# CONNECTOR_BUFFER.net
KiCad netlist of a schematic drawn in Altium Designer
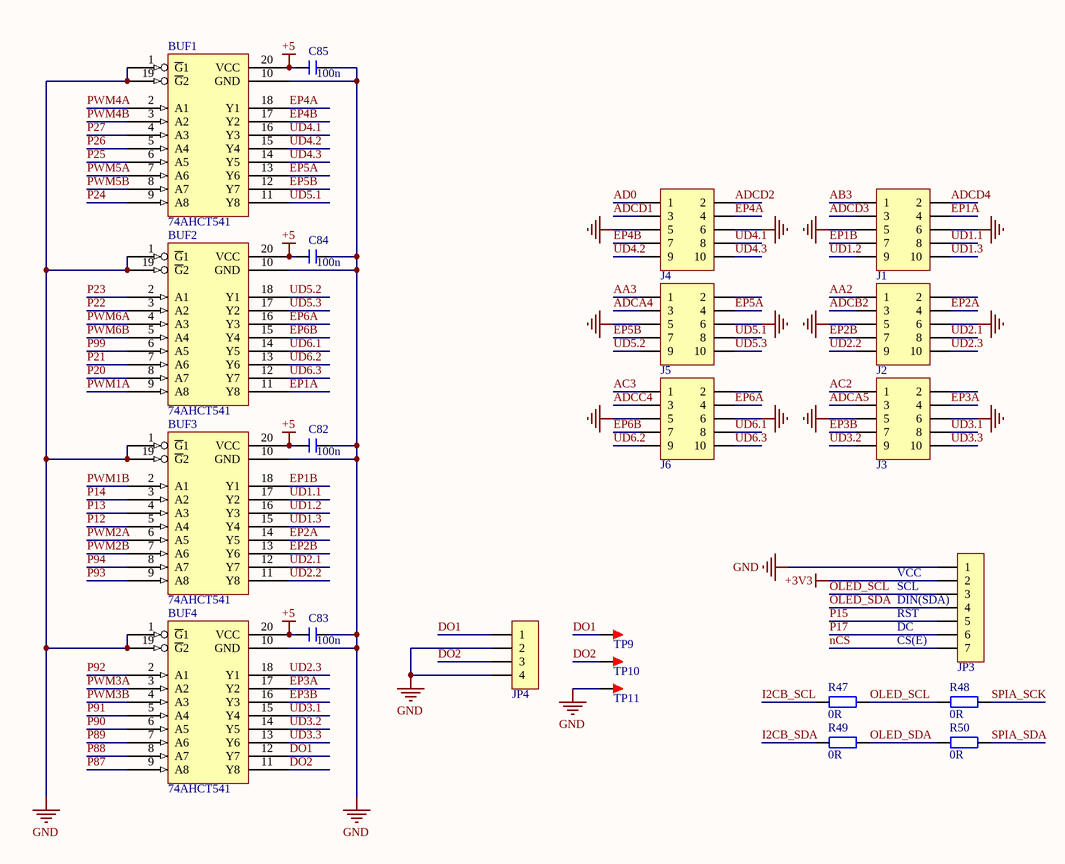
[diagram p0: CONNECTOR_BUFFER.SchDoc]

(export (version "E")
  (design (tool "Eeschema 10.0.6"))
  (components
    (comp (ref "BUF1")
      (value "74AHCT541")
      (footprint "TSSOP20_N")
      (libsource (lib "34 - 74系列芯片 -带电源") (part "74AHCT541"))
    )
    (comp (ref "BUF2")
      (value "74AHCT541")
      (footprint "TSSOP20_N")
      (libsource (lib "34 - 74系列芯片 -带电源") (part "74AHCT541"))
    )
    (comp (ref "BUF3")
      (value "74AHCT541")
      (footprint "TSSOP20_N")
      (libsource (lib "34 - 74系列芯片 -带电源") (part "74AHCT541"))
    )
    (comp (ref "BUF4")
      (value "74AHCT541")
      (footprint "TSSOP20_N")
      (libsource (lib "34 - 74系列芯片 -带电源") (part "74AHCT541"))
    )
    (comp (ref "C82")
      (value "100n")
      (footprint "C 0805_L")
      (description "贴片电容")
      (libsource (lib "01 - 电容-电阻-电感") (part "C"))
    )
    (comp (ref "C83")
      (value "100n")
      (footprint "C 0805_L")
      (description "贴片电容")
      (libsource (lib "01 - 电容-电阻-电感") (part "C"))
    )
    (comp (ref "C84")
      (value "100n")
      (footprint "C 0805_L")
      (description "贴片电容")
      (libsource (lib "01 - 电容-电阻-电感") (part "C"))
    )
    (comp (ref "C85")
      (value "100n")
      (footprint "C 0805_L")
      (description "贴片电容")
      (libsource (lib "01 - 电容-电阻-电感") (part "C"))
    )
    (comp (ref "J1")
      (value "Header 5X2")
      (footprint "IDC2.54-LI-2x5P")
      (description "5*2P接插件")
      (libsource (lib "18 - 接插件-脚距2.54mm (100mil) ") (part "Header 5X2"))
    )
    (comp (ref "J2")
      (value "Header 5X2")
      (footprint "IDC2.54-LI-2x5P")
      (description "5*2P接插件")
      (libsource (lib "18 - 接插件-脚距2.54mm (100mil) ") (part "Header 5X2"))
    )
    (comp (ref "J3")
      (value "Header 5X2")
      (footprint "IDC2.54-LI-2x5P")
      (description "5*2P接插件")
      (libsource (lib "18 - 接插件-脚距2.54mm (100mil) ") (part "Header 5X2"))
    )
    (comp (ref "J4")
      (value "Header 5X2")
      (footprint "IDC2.54-LI-2x5P")
      (description "5*2P接插件")
      (libsource (lib "18 - 接插件-脚距2.54mm (100mil) ") (part "Header 5X2"))
    )
    (comp (ref "J5")
      (value "Header 5X2")
      (footprint "IDC2.54-LI-2x5P")
      (description "5*2P接插件")
      (libsource (lib "18 - 接插件-脚距2.54mm (100mil) ") (part "Header 5X2"))
    )
    (comp (ref "J6")
      (value "Header 5X2")
      (footprint "IDC2.54-LI-2x5P")
      (description "5*2P接插件")
      (libsource (lib "18 - 接插件-脚距2.54mm (100mil) ") (part "Header 5X2"))
    )
    (comp (ref "JP3")
      (value "HDR-1X7")
      (footprint "HDR2.54-M-LI-7P")
      (description "7P接插件")
      (libsource (lib "18 - 接插件-脚距2.54mm (100mil) ") (part "Header 7"))
    )
    (comp (ref "JP4")
      (value "HDR-1X4")
      (footprint "HDR2.54-LI-4P")
      (description "4P接插件")
      (libsource (lib "18 - 接插件-脚距2.54mm (100mil) ") (part "Header 4"))
    )
    (comp (ref "R47")
      (value "0R")
      (footprint "R 0805_L")
      (description "贴片电阻")
      (libsource (lib "01 - 电容-电阻-电感") (part "R"))
    )
    (comp (ref "R48")
      (value "0R")
      (footprint "R 0805_L")
      (description "贴片电阻")
      (libsource (lib "01 - 电容-电阻-电感") (part "R"))
    )
    (comp (ref "R49")
      (value "0R")
      (footprint "R 0805_L")
      (description "贴片电阻")
      (libsource (lib "01 - 电容-电阻-电感") (part "R"))
    )
    (comp (ref "R50")
      (value "0R")
      (footprint "R 0805_L")
      (description "贴片电阻")
      (libsource (lib "01 - 电容-电阻-电感") (part "R"))
    )
    (comp (ref "TP9")
      (value "TEST TP")
      (footprint "TEST TP1.4_B")
      (description "测试环")
      (libsource (lib "10 - 未分类元器件") (part "TEST TP"))
    )
    (comp (ref "TP10")
      (value "TEST TP")
      (footprint "TEST TP1.4_B")
      (description "测试环")
      (libsource (lib "10 - 未分类元器件") (part "TEST TP"))
    )
    (comp (ref "TP11")
      (value "TEST TP")
      (footprint "TEST TP1.4_B")
      (description "测试环")
      (libsource (lib "10 - 未分类元器件") (part "TEST TP"))
    )
  )
  (nets
    (net (code "1") (name "+3V3") (class "Default")
      (node (ref "JP3") (pin "2") (pinfunction "2_2") (pintype "passive"))
    )
    (net (code "2") (name "+5") (class "Default")
      (node (ref "BUF1") (pin "20") (pinfunction "VCC_20") (pintype "passive"))
      (node (ref "BUF2") (pin "20") (pinfunction "VCC_20") (pintype "passive"))
      (node (ref "BUF3") (pin "20") (pinfunction "VCC_20") (pintype "passive"))
      (node (ref "BUF4") (pin "20") (pinfunction "VCC_20") (pintype "passive"))
      (node (ref "C82") (pin "2") (pinfunction "2_2") (pintype "passive"))
      (node (ref "C83") (pin "2") (pinfunction "2_2") (pintype "passive"))
      (node (ref "C84") (pin "2") (pinfunction "2_2") (pintype "passive"))
      (node (ref "C85") (pin "2") (pinfunction "2_2") (pintype "passive"))
    )
    (net (code "3") (name "/AA2") (class "Default")
      (node (ref "J2") (pin "1") (pinfunction "1_1") (pintype "passive"))
    )
    (net (code "4") (name "/AA3") (class "Default")
      (node (ref "J5") (pin "1") (pinfunction "1_1") (pintype "passive"))
    )
    (net (code "5") (name "/AB3") (class "Default")
      (node (ref "J1") (pin "1") (pinfunction "1_1") (pintype "passive"))
    )
    (net (code "6") (name "/AC2") (class "Default")
      (node (ref "J3") (pin "1") (pinfunction "1_1") (pintype "passive"))
    )
    (net (code "7") (name "/AC3") (class "Default")
      (node (ref "J6") (pin "1") (pinfunction "1_1") (pintype "passive"))
    )
    (net (code "8") (name "/AD0") (class "Default")
      (node (ref "J4") (pin "1") (pinfunction "1_1") (pintype "passive"))
    )
    (net (code "9") (name "/ADCA4") (class "Default")
      (node (ref "J5") (pin "3") (pinfunction "3_3") (pintype "passive"))
    )
    (net (code "10") (name "/ADCA5") (class "Default")
      (node (ref "J3") (pin "3") (pinfunction "3_3") (pintype "passive"))
    )
    (net (code "11") (name "/ADCB2") (class "Default")
      (node (ref "J2") (pin "3") (pinfunction "3_3") (pintype "passive"))
    )
    (net (code "12") (name "/ADCC4") (class "Default")
      (node (ref "J6") (pin "3") (pinfunction "3_3") (pintype "passive"))
    )
    (net (code "13") (name "/ADCD1") (class "Default")
      (node (ref "J4") (pin "3") (pinfunction "3_3") (pintype "passive"))
    )
    (net (code "14") (name "/ADCD2") (class "Default")
      (node (ref "J4") (pin "2") (pinfunction "2_2") (pintype "passive"))
    )
    (net (code "15") (name "/ADCD3") (class "Default")
      (node (ref "J1") (pin "3") (pinfunction "3_3") (pintype "passive"))
    )
    (net (code "16") (name "/ADCD4") (class "Default")
      (node (ref "J1") (pin "2") (pinfunction "2_2") (pintype "passive"))
    )
    (net (code "17") (name "/DO1") (class "Default")
      (node (ref "BUF4") (pin "12") (pinfunction "Y7_12") (pintype "tri_state"))
      (node (ref "JP4") (pin "1") (pinfunction "1_1") (pintype "passive"))
      (node (ref "TP9") (pin "1") (pinfunction "1_1") (pintype "passive"))
    )
    (net (code "18") (name "/DO2") (class "Default")
      (node (ref "BUF4") (pin "11") (pinfunction "Y8_11") (pintype "tri_state"))
      (node (ref "JP4") (pin "3") (pinfunction "3_3") (pintype "passive"))
      (node (ref "TP10") (pin "1") (pinfunction "1_1") (pintype "passive"))
    )
    (net (code "19") (name "/EP1A") (class "Default")
      (node (ref "BUF2") (pin "11") (pinfunction "Y8_11") (pintype "tri_state"))
      (node (ref "J1") (pin "4") (pinfunction "4_4") (pintype "passive"))
    )
    (net (code "20") (name "/EP1B") (class "Default")
      (node (ref "BUF3") (pin "18") (pinfunction "Y1_18") (pintype "tri_state"))
      (node (ref "J1") (pin "7") (pinfunction "7_7") (pintype "passive"))
    )
    (net (code "21") (name "/EP2A") (class "Default")
      (node (ref "BUF3") (pin "14") (pinfunction "Y5_14") (pintype "tri_state"))
      (node (ref "J2") (pin "4") (pinfunction "4_4") (pintype "passive"))
    )
    (net (code "22") (name "/EP2B") (class "Default")
      (node (ref "BUF3") (pin "13") (pinfunction "Y6_13") (pintype "tri_state"))
      (node (ref "J2") (pin "7") (pinfunction "7_7") (pintype "passive"))
    )
    (net (code "23") (name "/EP3A") (class "Default")
      (node (ref "BUF4") (pin "17") (pinfunction "Y2_17") (pintype "tri_state"))
      (node (ref "J3") (pin "4") (pinfunction "4_4") (pintype "passive"))
    )
    (net (code "24") (name "/EP3B") (class "Default")
      (node (ref "BUF4") (pin "16") (pinfunction "Y3_16") (pintype "tri_state"))
      (node (ref "J3") (pin "7") (pinfunction "7_7") (pintype "passive"))
    )
    (net (code "25") (name "/EP4A") (class "Default")
      (node (ref "BUF1") (pin "18") (pinfunction "Y1_18") (pintype "tri_state"))
      (node (ref "J4") (pin "4") (pinfunction "4_4") (pintype "passive"))
    )
    (net (code "26") (name "/EP4B") (class "Default")
      (node (ref "BUF1") (pin "17") (pinfunction "Y2_17") (pintype "tri_state"))
      (node (ref "J4") (pin "7") (pinfunction "7_7") (pintype "passive"))
    )
    (net (code "27") (name "/EP5A") (class "Default")
      (node (ref "BUF1") (pin "13") (pinfunction "Y6_13") (pintype "tri_state"))
      (node (ref "J5") (pin "4") (pinfunction "4_4") (pintype "passive"))
    )
    (net (code "28") (name "/EP5B") (class "Default")
      (node (ref "BUF1") (pin "12") (pinfunction "Y7_12") (pintype "tri_state"))
      (node (ref "J5") (pin "7") (pinfunction "7_7") (pintype "passive"))
    )
    (net (code "29") (name "/EP6A") (class "Default")
      (node (ref "BUF2") (pin "16") (pinfunction "Y3_16") (pintype "tri_state"))
      (node (ref "J6") (pin "4") (pinfunction "4_4") (pintype "passive"))
    )
    (net (code "30") (name "/EP6B") (class "Default")
      (node (ref "BUF2") (pin "15") (pinfunction "Y4_15") (pintype "tri_state"))
      (node (ref "J6") (pin "7") (pinfunction "7_7") (pintype "passive"))
    )
    (net (code "31") (name "/I2CB_SCL") (class "Default")
      (node (ref "R47") (pin "1") (pinfunction "1_1") (pintype "passive"))
    )
    (net (code "32") (name "/I2CB_SDA") (class "Default")
      (node (ref "R49") (pin "1") (pinfunction "1_1") (pintype "passive"))
    )
    (net (code "33") (name "/OLED_SCL") (class "Default")
      (node (ref "JP3") (pin "3") (pinfunction "3_3") (pintype "passive"))
      (node (ref "R47") (pin "2") (pinfunction "2_2") (pintype "passive"))
      (node (ref "R48") (pin "1") (pinfunction "1_1") (pintype "passive"))
    )
    (net (code "34") (name "/OLED_SDA") (class "Default")
      (node (ref "JP3") (pin "4") (pinfunction "4_4") (pintype "passive"))
      (node (ref "R49") (pin "2") (pinfunction "2_2") (pintype "passive"))
      (node (ref "R50") (pin "1") (pinfunction "1_1") (pintype "passive"))
    )
    (net (code "35") (name "/P12") (class "Default")
      (node (ref "BUF3") (pin "5") (pinfunction "A4_5") (pintype "input"))
    )
    (net (code "36") (name "/P13") (class "Default")
      (node (ref "BUF3") (pin "4") (pinfunction "A3_4") (pintype "input"))
    )
    (net (code "37") (name "/P14") (class "Default")
      (node (ref "BUF3") (pin "3") (pinfunction "A2_3") (pintype "input"))
    )
    (net (code "38") (name "/P15") (class "Default")
      (node (ref "JP3") (pin "5") (pinfunction "5_5") (pintype "passive"))
    )
    (net (code "39") (name "/P17") (class "Default")
      (node (ref "JP3") (pin "6") (pinfunction "6_6") (pintype "passive"))
    )
    (net (code "40") (name "/P20") (class "Default")
      (node (ref "BUF2") (pin "8") (pinfunction "A7_8") (pintype "input"))
    )
    (net (code "41") (name "/P21") (class "Default")
      (node (ref "BUF2") (pin "7") (pinfunction "A6_7") (pintype "input"))
    )
    (net (code "42") (name "/P22") (class "Default")
      (node (ref "BUF2") (pin "3") (pinfunction "A2_3") (pintype "input"))
    )
    (net (code "43") (name "/P23") (class "Default")
      (node (ref "BUF2") (pin "2") (pinfunction "A1_2") (pintype "input"))
    )
    (net (code "44") (name "/P24") (class "Default")
      (node (ref "BUF1") (pin "9") (pinfunction "A8_9") (pintype "input"))
    )
    (net (code "45") (name "/P25") (class "Default")
      (node (ref "BUF1") (pin "6") (pinfunction "A5_6") (pintype "input"))
    )
    (net (code "46") (name "/P26") (class "Default")
      (node (ref "BUF1") (pin "5") (pinfunction "A4_5") (pintype "input"))
    )
    (net (code "47") (name "/P27") (class "Default")
      (node (ref "BUF1") (pin "4") (pinfunction "A3_4") (pintype "input"))
    )
    (net (code "48") (name "/P87") (class "Default")
      (node (ref "BUF4") (pin "9") (pinfunction "A8_9") (pintype "input"))
    )
    (net (code "49") (name "/P88") (class "Default")
      (node (ref "BUF4") (pin "8") (pinfunction "A7_8") (pintype "input"))
    )
    (net (code "50") (name "/P89") (class "Default")
      (node (ref "BUF4") (pin "7") (pinfunction "A6_7") (pintype "input"))
    )
    (net (code "51") (name "/P90") (class "Default")
      (node (ref "BUF4") (pin "6") (pinfunction "A5_6") (pintype "input"))
    )
    (net (code "52") (name "/P91") (class "Default")
      (node (ref "BUF4") (pin "5") (pinfunction "A4_5") (pintype "input"))
    )
    (net (code "53") (name "/P92") (class "Default")
      (node (ref "BUF4") (pin "2") (pinfunction "A1_2") (pintype "input"))
    )
    (net (code "54") (name "/P93") (class "Default")
      (node (ref "BUF3") (pin "9") (pinfunction "A8_9") (pintype "input"))
    )
    (net (code "55") (name "/P94") (class "Default")
      (node (ref "BUF3") (pin "8") (pinfunction "A7_8") (pintype "input"))
    )
    (net (code "56") (name "/P99") (class "Default")
      (node (ref "BUF2") (pin "6") (pinfunction "A5_6") (pintype "input"))
    )
    (net (code "57") (name "/PWM1A") (class "Default")
      (node (ref "BUF2") (pin "9") (pinfunction "A8_9") (pintype "input"))
    )
    (net (code "58") (name "/PWM1B") (class "Default")
      (node (ref "BUF3") (pin "2") (pinfunction "A1_2") (pintype "input"))
    )
    (net (code "59") (name "/PWM2A") (class "Default")
      (node (ref "BUF3") (pin "6") (pinfunction "A5_6") (pintype "input"))
    )
    (net (code "60") (name "/PWM2B") (class "Default")
      (node (ref "BUF3") (pin "7") (pinfunction "A6_7") (pintype "input"))
    )
    (net (code "61") (name "/PWM3A") (class "Default")
      (node (ref "BUF4") (pin "3") (pinfunction "A2_3") (pintype "input"))
    )
    (net (code "62") (name "/PWM3B") (class "Default")
      (node (ref "BUF4") (pin "4") (pinfunction "A3_4") (pintype "input"))
    )
    (net (code "63") (name "/PWM4A") (class "Default")
      (node (ref "BUF1") (pin "2") (pinfunction "A1_2") (pintype "input"))
    )
    (net (code "64") (name "/PWM4B") (class "Default")
      (node (ref "BUF1") (pin "3") (pinfunction "A2_3") (pintype "input"))
    )
    (net (code "65") (name "/PWM5A") (class "Default")
      (node (ref "BUF1") (pin "7") (pinfunction "A6_7") (pintype "input"))
    )
    (net (code "66") (name "/PWM5B") (class "Default")
      (node (ref "BUF1") (pin "8") (pinfunction "A7_8") (pintype "input"))
    )
    (net (code "67") (name "/PWM6A") (class "Default")
      (node (ref "BUF2") (pin "4") (pinfunction "A3_4") (pintype "input"))
    )
    (net (code "68") (name "/PWM6B") (class "Default")
      (node (ref "BUF2") (pin "5") (pinfunction "A4_5") (pintype "input"))
    )
    (net (code "69") (name "/SPIA_SCK") (class "Default")
      (node (ref "R48") (pin "2") (pinfunction "2_2") (pintype "passive"))
    )
    (net (code "70") (name "/SPIA_SDA") (class "Default")
      (node (ref "R50") (pin "2") (pinfunction "2_2") (pintype "passive"))
    )
    (net (code "71") (name "/UD1.1") (class "Default")
      (node (ref "BUF3") (pin "17") (pinfunction "Y2_17") (pintype "tri_state"))
      (node (ref "J1") (pin "8") (pinfunction "8_8") (pintype "passive"))
    )
    (net (code "72") (name "/UD1.2") (class "Default")
      (node (ref "BUF3") (pin "16") (pinfunction "Y3_16") (pintype "tri_state"))
      (node (ref "J1") (pin "9") (pinfunction "9_9") (pintype "passive"))
    )
    (net (code "73") (name "/UD1.3") (class "Default")
      (node (ref "BUF3") (pin "15") (pinfunction "Y4_15") (pintype "tri_state"))
      (node (ref "J1") (pin "10") (pinfunction "10_10") (pintype "passive"))
    )
    (net (code "74") (name "/UD2.1") (class "Default")
      (node (ref "BUF3") (pin "12") (pinfunction "Y7_12") (pintype "tri_state"))
      (node (ref "J2") (pin "8") (pinfunction "8_8") (pintype "passive"))
    )
    (net (code "75") (name "/UD2.2") (class "Default")
      (node (ref "BUF3") (pin "11") (pinfunction "Y8_11") (pintype "tri_state"))
      (node (ref "J2") (pin "9") (pinfunction "9_9") (pintype "passive"))
    )
    (net (code "76") (name "/UD2.3") (class "Default")
      (node (ref "BUF4") (pin "18") (pinfunction "Y1_18") (pintype "tri_state"))
      (node (ref "J2") (pin "10") (pinfunction "10_10") (pintype "passive"))
    )
    (net (code "77") (name "/UD3.1") (class "Default")
      (node (ref "BUF4") (pin "15") (pinfunction "Y4_15") (pintype "tri_state"))
      (node (ref "J3") (pin "8") (pinfunction "8_8") (pintype "passive"))
    )
    (net (code "78") (name "/UD3.2") (class "Default")
      (node (ref "BUF4") (pin "14") (pinfunction "Y5_14") (pintype "tri_state"))
      (node (ref "J3") (pin "9") (pinfunction "9_9") (pintype "passive"))
    )
    (net (code "79") (name "/UD3.3") (class "Default")
      (node (ref "BUF4") (pin "13") (pinfunction "Y6_13") (pintype "tri_state"))
      (node (ref "J3") (pin "10") (pinfunction "10_10") (pintype "passive"))
    )
    (net (code "80") (name "/UD4.1") (class "Default")
      (node (ref "BUF1") (pin "16") (pinfunction "Y3_16") (pintype "tri_state"))
      (node (ref "J4") (pin "8") (pinfunction "8_8") (pintype "passive"))
    )
    (net (code "81") (name "/UD4.2") (class "Default")
      (node (ref "BUF1") (pin "15") (pinfunction "Y4_15") (pintype "tri_state"))
      (node (ref "J4") (pin "9") (pinfunction "9_9") (pintype "passive"))
    )
    (net (code "82") (name "/UD4.3") (class "Default")
      (node (ref "BUF1") (pin "14") (pinfunction "Y5_14") (pintype "tri_state"))
      (node (ref "J4") (pin "10") (pinfunction "10_10") (pintype "passive"))
    )
    (net (code "83") (name "/UD5.1") (class "Default")
      (node (ref "BUF1") (pin "11") (pinfunction "Y8_11") (pintype "tri_state"))
      (node (ref "J5") (pin "8") (pinfunction "8_8") (pintype "passive"))
    )
    (net (code "84") (name "/UD5.2") (class "Default")
      (node (ref "BUF2") (pin "18") (pinfunction "Y1_18") (pintype "tri_state"))
      (node (ref "J5") (pin "9") (pinfunction "9_9") (pintype "passive"))
    )
    (net (code "85") (name "/UD5.3") (class "Default")
      (node (ref "BUF2") (pin "17") (pinfunction "Y2_17") (pintype "tri_state"))
      (node (ref "J5") (pin "10") (pinfunction "10_10") (pintype "passive"))
    )
    (net (code "86") (name "/UD6.1") (class "Default")
      (node (ref "BUF2") (pin "14") (pinfunction "Y5_14") (pintype "tri_state"))
      (node (ref "J6") (pin "8") (pinfunction "8_8") (pintype "passive"))
    )
    (net (code "87") (name "/UD6.2") (class "Default")
      (node (ref "BUF2") (pin "13") (pinfunction "Y6_13") (pintype "tri_state"))
      (node (ref "J6") (pin "9") (pinfunction "9_9") (pintype "passive"))
    )
    (net (code "88") (name "/UD6.3") (class "Default")
      (node (ref "BUF2") (pin "12") (pinfunction "Y7_12") (pintype "tri_state"))
      (node (ref "J6") (pin "10") (pinfunction "10_10") (pintype "passive"))
    )
    (net (code "89") (name "/nCS") (class "Default")
      (node (ref "JP3") (pin "7") (pinfunction "7_7") (pintype "passive"))
    )
    (net (code "90") (name "GND") (class "Default")
      (node (ref "BUF1") (pin "1") (pinfunction "~{G}1_1") (pintype "input"))
      (node (ref "BUF1") (pin "10") (pinfunction "GND_10") (pintype "passive"))
      (node (ref "BUF1") (pin "19") (pinfunction "~{G}2_19") (pintype "input"))
      (node (ref "BUF2") (pin "1") (pinfunction "~{G}1_1") (pintype "input"))
      (node (ref "BUF2") (pin "10") (pinfunction "GND_10") (pintype "passive"))
      (node (ref "BUF2") (pin "19") (pinfunction "~{G}2_19") (pintype "input"))
      (node (ref "BUF3") (pin "1") (pinfunction "~{G}1_1") (pintype "input"))
      (node (ref "BUF3") (pin "10") (pinfunction "GND_10") (pintype "passive"))
      (node (ref "BUF3") (pin "19") (pinfunction "~{G}2_19") (pintype "input"))
      (node (ref "BUF4") (pin "1") (pinfunction "~{G}1_1") (pintype "input"))
      (node (ref "BUF4") (pin "10") (pinfunction "GND_10") (pintype "passive"))
      (node (ref "BUF4") (pin "19") (pinfunction "~{G}2_19") (pintype "input"))
      (node (ref "C82") (pin "1") (pinfunction "1_1") (pintype "passive"))
      (node (ref "C83") (pin "1") (pinfunction "1_1") (pintype "passive"))
      (node (ref "C84") (pin "1") (pinfunction "1_1") (pintype "passive"))
      (node (ref "C85") (pin "1") (pinfunction "1_1") (pintype "passive"))
      (node (ref "J1") (pin "5") (pinfunction "5_5") (pintype "passive"))
      (node (ref "J1") (pin "6") (pinfunction "6_6") (pintype "passive"))
      (node (ref "J2") (pin "5") (pinfunction "5_5") (pintype "passive"))
      (node (ref "J2") (pin "6") (pinfunction "6_6") (pintype "passive"))
      (node (ref "J3") (pin "5") (pinfunction "5_5") (pintype "passive"))
      (node (ref "J3") (pin "6") (pinfunction "6_6") (pintype "passive"))
      (node (ref "J4") (pin "5") (pinfunction "5_5") (pintype "passive"))
      (node (ref "J4") (pin "6") (pinfunction "6_6") (pintype "passive"))
      (node (ref "J5") (pin "5") (pinfunction "5_5") (pintype "passive"))
      (node (ref "J5") (pin "6") (pinfunction "6_6") (pintype "passive"))
      (node (ref "J6") (pin "5") (pinfunction "5_5") (pintype "passive"))
      (node (ref "J6") (pin "6") (pinfunction "6_6") (pintype "passive"))
      (node (ref "JP3") (pin "1") (pinfunction "1_1") (pintype "passive"))
      (node (ref "JP4") (pin "2") (pinfunction "2_2") (pintype "passive"))
      (node (ref "JP4") (pin "4") (pinfunction "4_4") (pintype "passive"))
      (node (ref "TP11") (pin "1") (pinfunction "1_1") (pintype "passive"))
    )
    (net (code "91") (name "unconnected-(J2-Pad2)") (class "Default")
      (node (ref "J2") (pin "2") (pinfunction "2_2") (pintype "passive"))
    )
    (net (code "92") (name "unconnected-(J3-Pad2)") (class "Default")
      (node (ref "J3") (pin "2") (pinfunction "2_2") (pintype "passive"))
    )
    (net (code "93") (name "unconnected-(J5-Pad2)") (class "Default")
      (node (ref "J5") (pin "2") (pinfunction "2_2") (pintype "passive"))
    )
    (net (code "94") (name "unconnected-(J6-Pad2)") (class "Default")
      (node (ref "J6") (pin "2") (pinfunction "2_2") (pintype "passive"))
    )
  )
)
